# DIO-BNC_CH4-7.net
KiCad netlist of a schematic drawn in Altium Designer
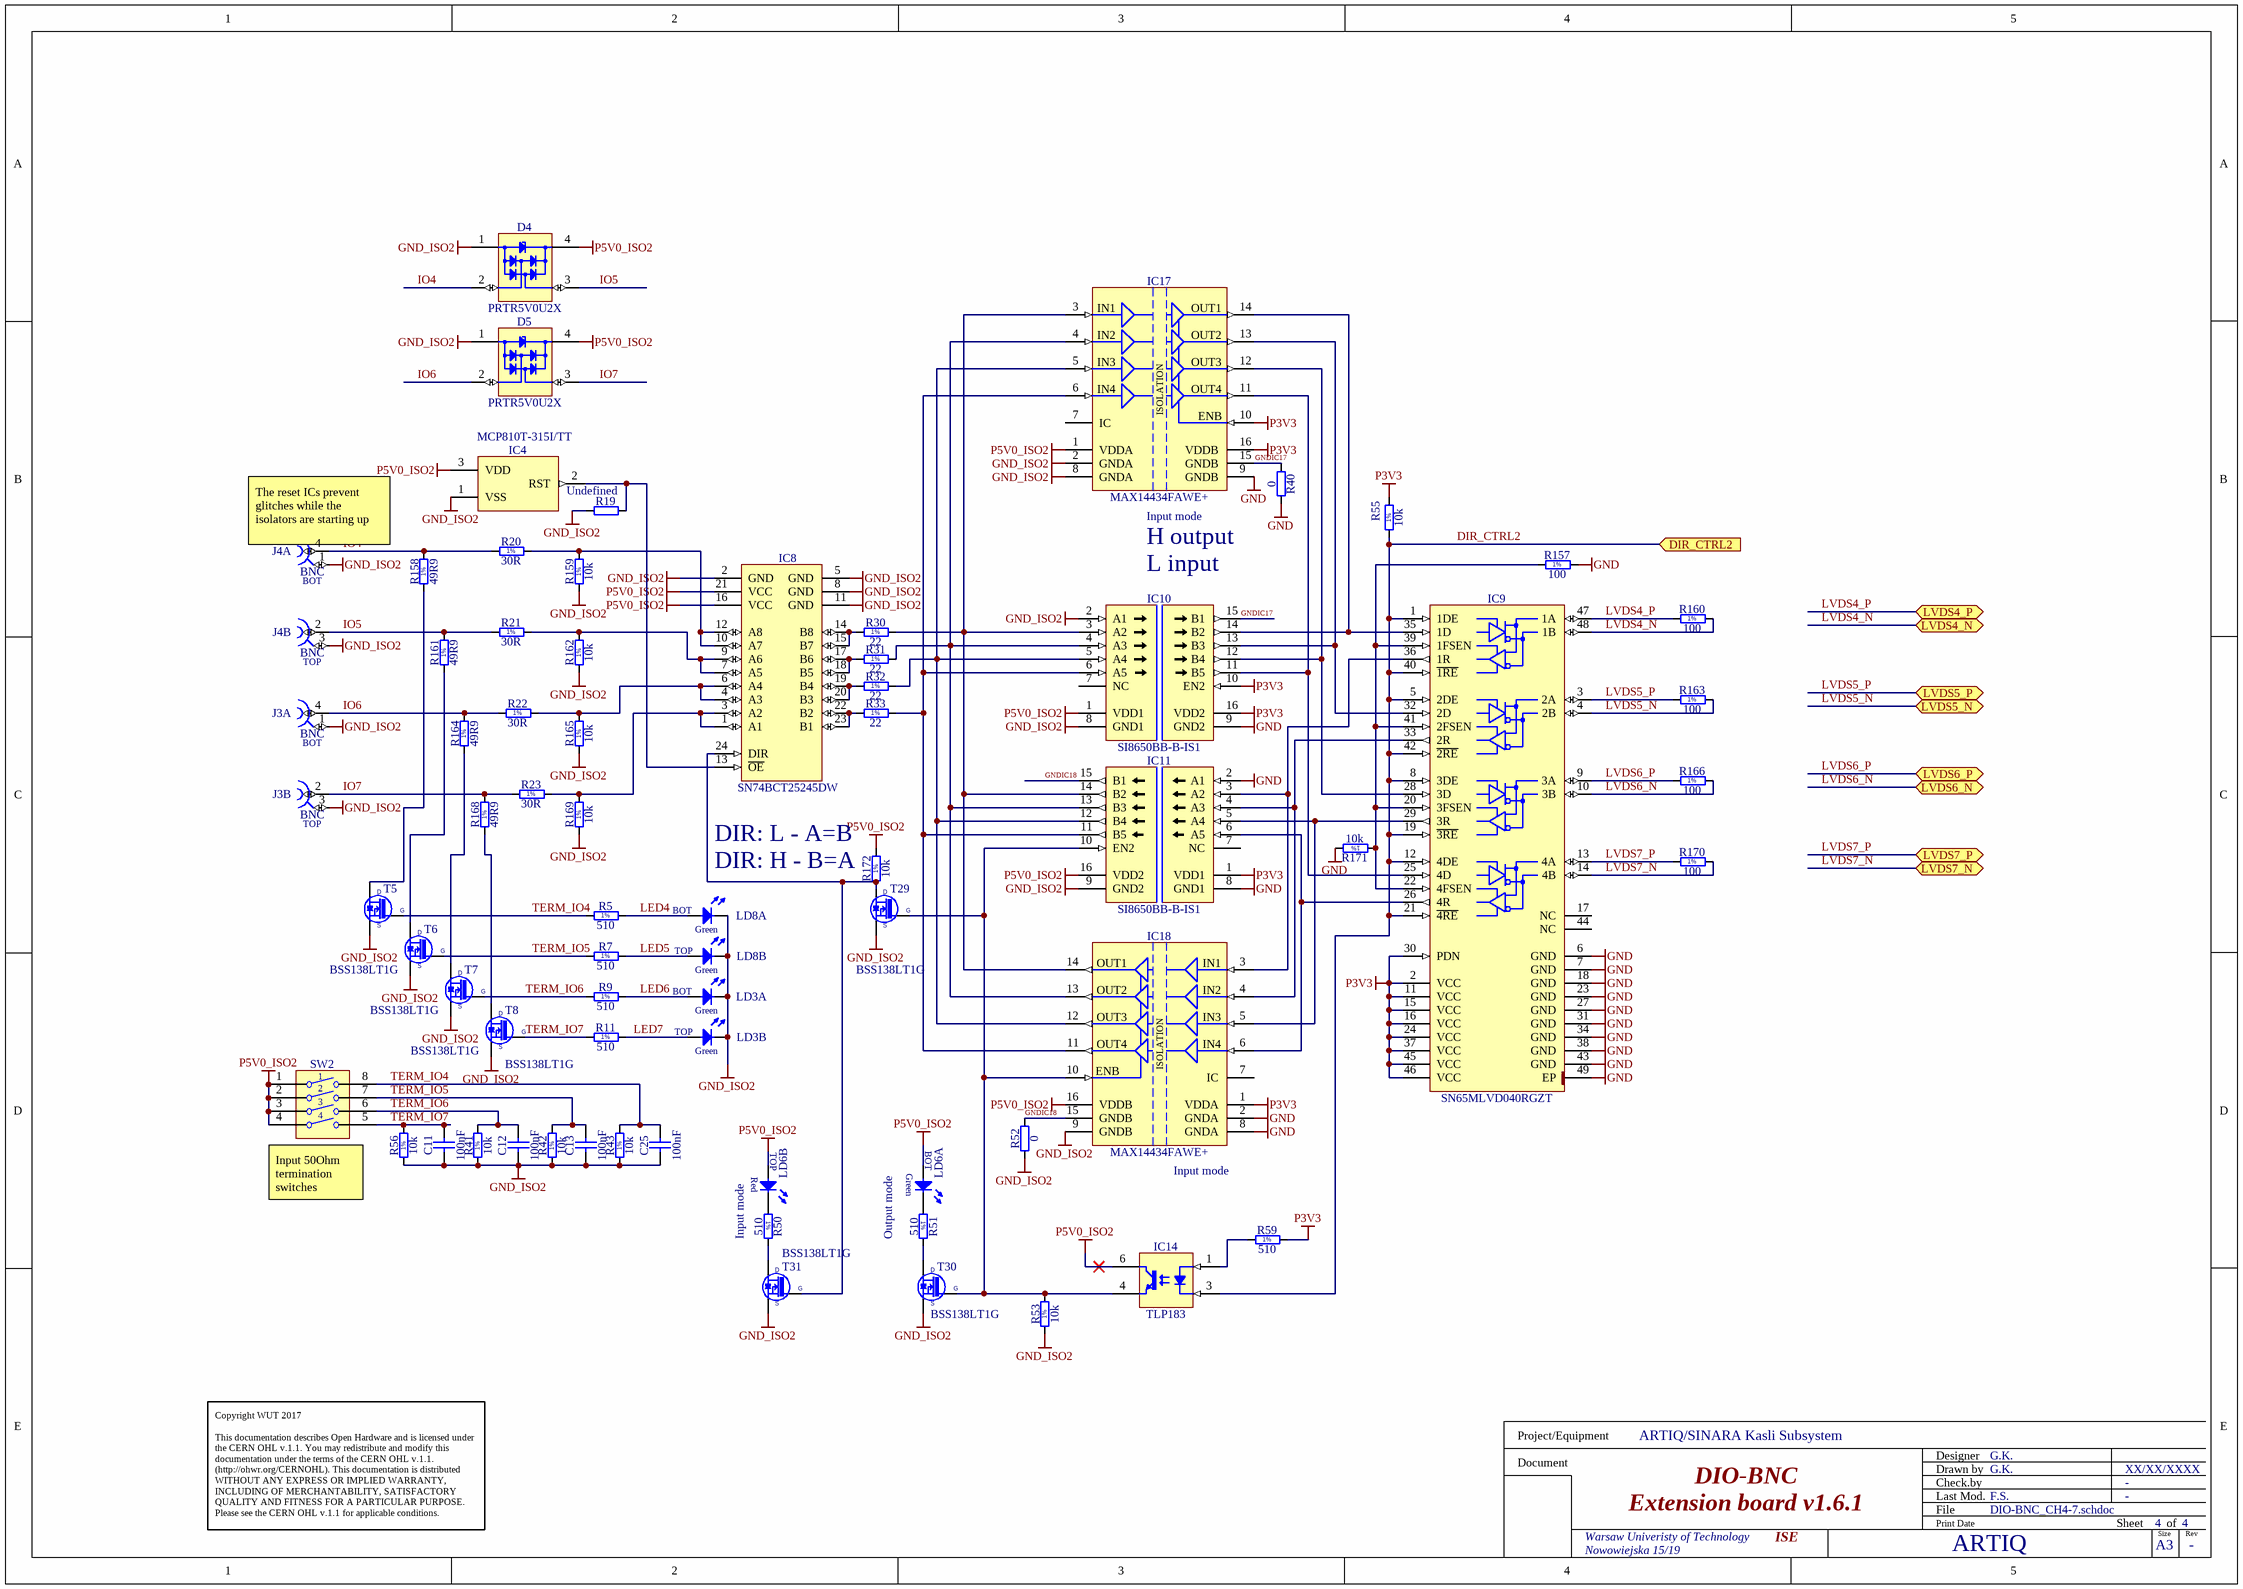
[diagram p0: DIO-BNC_CH4-7.schdoc]

(export (version "E")
  (design (tool "Eeschema 10.0.6"))
  (components
    (comp (ref "C11")
      (value "100nF")
      (footprint "CAPC1005X55N")
      (description "Non-polarised capacitor")
      (fields
        (field (name "PART NUMBER") "CC0402_100NF_16V_10%_X5R")
        (field (name "VOLTAGE") "16V")
        (field (name "AUTHOR") "CERN DEM JLC")
      )
      (libsource (lib "Capacitors") (part "Capacitor - non polarized"))
    )
    (comp (ref "C12")
      (value "100nF")
      (footprint "CAPC1005X55N")
      (description "Non-polarised capacitor")
      (fields
        (field (name "PART NUMBER") "CC0402_100NF_16V_10%_X5R")
        (field (name "VOLTAGE") "16V")
        (field (name "AUTHOR") "CERN DEM JLC")
      )
      (libsource (lib "Capacitors") (part "Capacitor - non polarized"))
    )
    (comp (ref "C13")
      (value "100nF")
      (footprint "CAPC1005X55N")
      (description "Non-polarised capacitor")
      (fields
        (field (name "PART NUMBER") "CC0402_100NF_16V_10%_X5R")
        (field (name "VOLTAGE") "16V")
        (field (name "AUTHOR") "CERN DEM JLC")
      )
      (libsource (lib "Capacitors") (part "Capacitor - non polarized"))
    )
    (comp (ref "C25")
      (value "100nF")
      (footprint "CAPC1005X55N")
      (description "Non-polarised capacitor")
      (fields
        (field (name "PART NUMBER") "CC0402_100NF_16V_10%_X5R")
        (field (name "VOLTAGE") "16V")
        (field (name "AUTHOR") "CERN DEM JLC")
      )
      (libsource (lib "Capacitors") (part "Capacitor - non polarized"))
    )
    (comp (ref "D4")
      (value "PRTR5V0U2X")
      (footprint "SOT190P230X110-4N")
      (description "Ultra Low Capacitance Double Rail-to-Rail ESD Protection Diode")
      (fields
        (field (name "VOLTAGE") "5.5V")
        (field (name "MANUFACTURER") "NXP SEMICONDUCTORS")
        (field (name "AUTHOR") "CERN DEM JLC")
      )
      (libsource (lib "ICs And Semiconductors") (part "PRTR5V0U2X"))
    )
    (comp (ref "D5")
      (value "PRTR5V0U2X")
      (footprint "SOT190P230X110-4N")
      (description "Ultra Low Capacitance Double Rail-to-Rail ESD Protection Diode")
      (fields
        (field (name "VOLTAGE") "5.5V")
        (field (name "MANUFACTURER") "NXP SEMICONDUCTORS")
        (field (name "AUTHOR") "CERN DEM JLC")
      )
      (libsource (lib "ICs And Semiconductors") (part "PRTR5V0U2X"))
    )
    (comp (ref "IC4")
      (value "MCP810T-315I/TT")
      (footprint "SOT95P237X112-3N")
      (description "3.075V Microcontroller Supervisory Circuit With Push-Pull Output")
      (fields (field (name "MANUFACTURER") "MICROCHIP TECHNOLOGY") (field (name "AUTHOR") "GK"))
      (libsource (lib "LIBRARY_SCH") (part "VMON_MCP810"))
    )
    (comp (ref "IC8")
      (value "SN74BCT25245DW")
      (footprint "SOIC127P1030X265-24N")
      (description "25 Ohms Octal Bus Transceiver With 3-State Outputs")
      (fields (field (name "MANUFACTURER") "TEXAS INSTRUMENTS") (field (name "AUTHOR") "CERN DEM JLC"))
      (libsource (lib "ICs And Semiconductors") (part "7425245"))
    )
    (comp (ref "IC9")
      (value "SN65MLVD040RGZT")
      (footprint "QFN50P700X700X100-49N-S420")
      (description "4-Channel Half-Duplex M-LVDS Line Transceiver")
      (fields (field (name "MANUFACTURER") "TEXAS INSTRUMENTS") (field (name "AUTHOR") "CERN DEM JLC"))
      (libsource (lib "ICs And Semiconductors") (part "SN65MLVD040"))
    )
    (comp (ref "IC10")
      (value "SI8650BB-B-IS1")
      (footprint "SOIC127P600X175-16N")
      (description "Low Power Five-Channel Digital Isolator")
      (fields
        (field (name "MANUFACTURER") "SKYWORKS")
        (field (name "MANUFACTURER PART NUMBER") "SI8651BB-B-IS1")
        (field (name "AUTHOR") "CERN DEM HF")
      )
      (libsource (lib "ICs And Semiconductors") (part "Si8650"))
    )
    (comp (ref "IC11")
      (value "SI8650BB-B-IS1")
      (footprint "SOIC127P600X175-16N")
      (description "Low Power Five-Channel Digital Isolator")
      (fields
        (field (name "MANUFACTURER") "SKYWORKS")
        (field (name "MANUFACTURER PART NUMBER") "SI8651BB-B-IS1")
        (field (name "AUTHOR") "CERN DEM HF")
      )
      (libsource (lib "") (part "Si8650_1"))
    )
    (comp (ref "IC14")
      (value "TLP183")
      (footprint "TOSHIBA_11-4M1S")
      (description "Single Optocoupler")
      (fields (field (name "MANUFACTURER") "TOSHIBA") (field (name "AUTHOR") "CERN DEM JMW"))
      (libsource (lib "ICs And Semiconductors") (part "Optocoupler Type1"))
    )
    (comp (ref "IC17")
      (value "MAX14434FAWE+")
      (footprint "SOIC127P1030X265-16N")
      (description "Four-Channel, Fast, Low-Power, 5kVRMS Digital Isolators")
      (fields (field (name "MANUFACTURER") "MAXIM") (field (name "AUTHOR") "CERN DEM HF"))
      (libsource (lib "ICs And Semiconductors") (part "MAX14434"))
    )
    (comp (ref "IC18")
      (value "MAX14434FAWE+")
      (footprint "SOIC127P1030X265-16N")
      (description "Four-Channel, Fast, Low-Power, 5kVRMS Digital Isolators")
      (fields (field (name "MANUFACTURER") "MAXIM") (field (name "AUTHOR") "CERN DEM HF"))
      (libsource (lib "ICs And Semiconductors") (part "MAX14434"))
    )
    (comp (ref "J3")
      (value "BNC")
      (footprint "RENHOTEC_RHT-610-0049")
      (description "Dual Right Angle 50 Ohm BNC Jack, White Valox Case")
      (fields
        (field (name "PART NUMBER") "RENHOTEC_RHT-610-0049")
        (field (name "MANUFACTURER") "RENHOTEC")
        (field (name "AUTHOR") "GK")
      )
      (libsource (lib "LIBRARY_SCH") (part "CON_BNC_DUAL"))
    )
    (comp (ref "J4")
      (value "BNC")
      (footprint "RENHOTEC_RHT-610-0049")
      (description "Dual Right Angle 50 Ohm BNC Jack, White Valox Case")
      (fields
        (field (name "PART NUMBER") "RENHOTEC_RHT-610-0049")
        (field (name "MANUFACTURER") "RENHOTEC")
        (field (name "AUTHOR") "GK")
      )
      (libsource (lib "LIBRARY_SCH") (part "CON_BNC_DUAL"))
    )
    (comp (ref "LD3")
      (value "Green/Green")
      (footprint "LED_DIALIGHT_571-0122F")
      (description "LED x2 Green 1C2A-BOT_3C4A-TOP")
      (fields
        (field (name "PART NUMBER") "LED_DIALIGHT_571-0122F")
        (field (name "MANUFACTURER") "DIALIGHT")
        (field (name "AUTHOR") "CERN DEM JLC")
      )
      (libsource (lib "ICs And Semiconductors") (part "LED x2 Green 1C2A-BOT_3C4A-TOP"))
    )
    (comp (ref "LD6")
      (value "Red/Green")
      (footprint "LED_DIALIGHT_571-0112F")
      (description "2x LED  Botom Green, Top Red")
      (fields
        (field (name "PART NUMBER") "LED_DIALIGHT_571-0112F")
        (field (name "MANUFACTURER") "DIALIGHT")
        (field (name "AUTHOR") "CERN DEM JLC")
      )
      (libsource (lib "ICs And Semiconductors") (part "LED x2 G-1C2A-BOT_R-3C4A-TOP"))
    )
    (comp (ref "LD8")
      (value "Green/Green")
      (footprint "LED_DIALIGHT_571-0122F")
      (description "LED x2 Green 1C2A-BOT_3C4A-TOP")
      (fields
        (field (name "PART NUMBER") "LED_DIALIGHT_571-0122F")
        (field (name "MANUFACTURER") "DIALIGHT")
        (field (name "AUTHOR") "CERN DEM JLC")
      )
      (libsource (lib "ICs And Semiconductors") (part "LED x2 Green 1C2A-BOT_3C4A-TOP"))
    )
    (comp (ref "R5")
      (value "510")
      (footprint "RESC1005X40N")
      (description "Resistor - 1%")
      (fields
        (field (name "PART NUMBER") "R0402_510R_1%_0.0625W_100PPM")
        (field (name "POWER") "0.0625W")
        (field (name "AUTHOR") "CERN DEM JLC")
      )
      (libsource (lib "Resistors") (part "Resistor - 1%"))
    )
    (comp (ref "R7")
      (value "510")
      (footprint "RESC1005X40N")
      (description "Resistor - 1%")
      (fields
        (field (name "PART NUMBER") "R0402_510R_1%_0.0625W_100PPM")
        (field (name "POWER") "0.0625W")
        (field (name "AUTHOR") "CERN DEM JLC")
      )
      (libsource (lib "Resistors") (part "Resistor - 1%"))
    )
    (comp (ref "R9")
      (value "510")
      (footprint "RESC1005X40N")
      (description "Resistor - 1%")
      (fields
        (field (name "PART NUMBER") "R0402_510R_1%_0.0625W_100PPM")
        (field (name "POWER") "0.0625W")
        (field (name "AUTHOR") "CERN DEM JLC")
      )
      (libsource (lib "Resistors") (part "Resistor - 1%"))
    )
    (comp (ref "R11")
      (value "510")
      (footprint "RESC1005X40N")
      (description "Resistor - 1%")
      (fields
        (field (name "PART NUMBER") "R0402_510R_1%_0.0625W_100PPM")
        (field (name "POWER") "0.0625W")
        (field (name "AUTHOR") "CERN DEM JLC")
      )
      (libsource (lib "Resistors") (part "Resistor - 1%"))
    )
    (comp (ref "R19")
      (value "Undefined")
      (footprint "RESC1005X40N")
      (description "Resistor")
      (fields (field (name "PART NUMBER") "R0402_NO-VALUE") (field (name "AUTHOR") "CERN DEM JLC"))
      (libsource (lib "Resistors") (part "Resistor"))
    )
    (comp (ref "R20")
      (value "30R")
      (footprint "RESC3225X70N")
      (description "Resistor - 5%")
      (fields
        (field (name "PART NUMBER") "R1210_30R_5%_0.5W_200ppm")
        (field (name "POWER") "0.5W")
        (field (name "AUTHOR") "CERN DEM JMW")
      )
      (libsource (lib "LIBRARY_SCH") (part "R1210_30R_5%_0.5W_200PPM"))
    )
    (comp (ref "R21")
      (value "30R")
      (footprint "RESC3225X70N")
      (description "Resistor - 5%")
      (fields
        (field (name "PART NUMBER") "R1210_30R_5%_0.5W_200ppm")
        (field (name "POWER") "0.5W")
        (field (name "AUTHOR") "CERN DEM JMW")
      )
      (libsource (lib "LIBRARY_SCH") (part "R1210_30R_5%_0.5W_200PPM"))
    )
    (comp (ref "R22")
      (value "30R")
      (footprint "RESC3225X70N")
      (description "Resistor - 5%")
      (fields
        (field (name "PART NUMBER") "R1210_30R_5%_0.5W_200ppm")
        (field (name "POWER") "0.5W")
        (field (name "AUTHOR") "CERN DEM JMW")
      )
      (libsource (lib "LIBRARY_SCH") (part "R1210_30R_5%_0.5W_200PPM"))
    )
    (comp (ref "R23")
      (value "30R")
      (footprint "RESC3225X70N")
      (description "Resistor - 5%")
      (fields
        (field (name "PART NUMBER") "R1210_30R_5%_0.5W_200ppm")
        (field (name "POWER") "0.5W")
        (field (name "AUTHOR") "CERN DEM JMW")
      )
      (libsource (lib "LIBRARY_SCH") (part "R1210_30R_5%_0.5W_200PPM"))
    )
    (comp (ref "R30")
      (value "22")
      (footprint "RESC1005X40N")
      (description "Resistor - 1%")
      (fields
        (field (name "PART NUMBER") "R0402_22R_1%_0.0625W_100PPM")
        (field (name "POWER") "0.0625W")
        (field (name "AUTHOR") "CERN DEM JLC")
      )
      (libsource (lib "Resistors") (part "Resistor - 1%"))
    )
    (comp (ref "R31")
      (value "22")
      (footprint "RESC1005X40N")
      (description "Resistor - 1%")
      (fields
        (field (name "PART NUMBER") "R0402_22R_1%_0.0625W_100PPM")
        (field (name "POWER") "0.0625W")
        (field (name "AUTHOR") "CERN DEM JLC")
      )
      (libsource (lib "Resistors") (part "Resistor - 1%"))
    )
    (comp (ref "R32")
      (value "22")
      (footprint "RESC1005X40N")
      (description "Resistor - 1%")
      (fields
        (field (name "PART NUMBER") "R0402_22R_1%_0.0625W_100PPM")
        (field (name "POWER") "0.0625W")
        (field (name "AUTHOR") "CERN DEM JLC")
      )
      (libsource (lib "Resistors") (part "Resistor - 1%"))
    )
    (comp (ref "R33")
      (value "22")
      (footprint "RESC1005X40N")
      (description "Resistor - 1%")
      (fields
        (field (name "PART NUMBER") "R0402_22R_1%_0.0625W_100PPM")
        (field (name "POWER") "0.0625W")
        (field (name "AUTHOR") "CERN DEM JLC")
      )
      (libsource (lib "Resistors") (part "Resistor - 1%"))
    )
    (comp (ref "R40")
      (value "0")
      (footprint "RESC1005X40N")
      (description "Resistor")
      (fields
        (field (name "PART NUMBER") "R0402_0R_JUMPER")
        (field (name "MANUFACTURER") "GENERIC")
        (field (name "AUTHOR") "CERN DEM JLC")
      )
      (libsource (lib "Resistors") (part "Resistor"))
    )
    (comp (ref "R41")
      (value "10k")
      (footprint "RESC1005X40N")
      (description "Resistor - 1%")
      (fields
        (field (name "PART NUMBER") "R0402_10K_1%_0.0625W_100PPM")
        (field (name "POWER") "0.0625W")
        (field (name "AUTHOR") "CERN DEM JLC")
      )
      (libsource (lib "Resistors") (part "Resistor - 1%"))
    )
    (comp (ref "R42")
      (value "10k")
      (footprint "RESC1005X40N")
      (description "Resistor - 1%")
      (fields
        (field (name "PART NUMBER") "R0402_10K_1%_0.0625W_100PPM")
        (field (name "POWER") "0.0625W")
        (field (name "AUTHOR") "CERN DEM JLC")
      )
      (libsource (lib "Resistors") (part "Resistor - 1%"))
    )
    (comp (ref "R43")
      (value "10k")
      (footprint "RESC1005X40N")
      (description "Resistor - 1%")
      (fields
        (field (name "PART NUMBER") "R0402_10K_1%_0.0625W_100PPM")
        (field (name "POWER") "0.0625W")
        (field (name "AUTHOR") "CERN DEM JLC")
      )
      (libsource (lib "Resistors") (part "Resistor - 1%"))
    )
    (comp (ref "R50")
      (value "510")
      (footprint "RESC1005X40N")
      (description "Resistor - 1%")
      (fields
        (field (name "PART NUMBER") "R0402_510R_1%_0.0625W_100PPM")
        (field (name "POWER") "0.0625W")
        (field (name "AUTHOR") "CERN DEM JLC")
      )
      (libsource (lib "Resistors") (part "Resistor - 1%"))
    )
    (comp (ref "R51")
      (value "510")
      (footprint "RESC1005X40N")
      (description "Resistor - 1%")
      (fields
        (field (name "PART NUMBER") "R0402_510R_1%_0.0625W_100PPM")
        (field (name "POWER") "0.0625W")
        (field (name "AUTHOR") "CERN DEM JLC")
      )
      (libsource (lib "Resistors") (part "Resistor - 1%"))
    )
    (comp (ref "R52")
      (value "0")
      (footprint "RESC1005X40N")
      (description "Resistor")
      (fields
        (field (name "PART NUMBER") "R0402_0R_JUMPER")
        (field (name "MANUFACTURER") "GENERIC")
        (field (name "AUTHOR") "CERN DEM JLC")
      )
      (libsource (lib "Resistors") (part "Resistor"))
    )
    (comp (ref "R53")
      (value "10k")
      (footprint "RESC1005X40N")
      (description "Resistor - 1%")
      (fields
        (field (name "PART NUMBER") "R0402_10K_1%_0.0625W_100PPM")
        (field (name "POWER") "0.0625W")
        (field (name "AUTHOR") "CERN DEM JLC")
      )
      (libsource (lib "Resistors") (part "Resistor - 1%"))
    )
    (comp (ref "R55")
      (value "10k")
      (footprint "RESC1005X40N")
      (description "Resistor - 1%")
      (fields
        (field (name "PART NUMBER") "R0402_10K_1%_0.0625W_100PPM")
        (field (name "POWER") "0.0625W")
        (field (name "AUTHOR") "CERN DEM JLC")
      )
      (libsource (lib "Resistors") (part "Resistor - 1%"))
    )
    (comp (ref "R56")
      (value "10k")
      (footprint "RESC1005X40N")
      (description "Resistor - 1%")
      (fields
        (field (name "PART NUMBER") "R0402_10K_1%_0.0625W_100PPM")
        (field (name "POWER") "0.0625W")
        (field (name "AUTHOR") "CERN DEM JLC")
      )
      (libsource (lib "Resistors") (part "Resistor - 1%"))
    )
    (comp (ref "R59")
      (value "510")
      (footprint "RESC1005X40N")
      (description "Resistor - 1%")
      (fields
        (field (name "PART NUMBER") "R0402_510R_1%_0.0625W_100PPM")
        (field (name "POWER") "0.0625W")
        (field (name "AUTHOR") "CERN DEM JLC")
      )
      (libsource (lib "Resistors") (part "Resistor - 1%"))
    )
    (comp (ref "R157")
      (value "100")
      (footprint "RESC1005X40N")
      (description "Resistor - 1%")
      (fields
        (field (name "PART NUMBER") "R0402_100R_1%_0.1W_100PPM")
        (field (name "POWER") "0.1W")
        (field (name "AUTHOR") "CERN DEM JLC")
      )
      (libsource (lib "Resistors") (part "Resistor - 1%"))
    )
    (comp (ref "R158")
      (value "49R9")
      (footprint "RESC3225X70N")
      (description "Resistor - 1%")
      (fields
        (field (name "PART NUMBER") "R1210_49R9_1%_0.5W_100PPM_VISHAY_CRCW")
        (field (name "POWER") "0.5W")
        (field (name "AUTHOR") "CERN DEM JMW")
      )
      (libsource (lib "Resistors") (part "Resistor - 1%"))
    )
    (comp (ref "R159")
      (value "10k")
      (footprint "RESC1005X40N")
      (description "Resistor - 1%")
      (fields
        (field (name "PART NUMBER") "R0402_10K_1%_0.0625W_100PPM")
        (field (name "POWER") "0.0625W")
        (field (name "AUTHOR") "CERN DEM JLC")
      )
      (libsource (lib "Resistors") (part "Resistor - 1%"))
    )
    (comp (ref "R160")
      (value "100")
      (footprint "RESC1005X40N")
      (description "Resistor - 1%")
      (fields
        (field (name "PART NUMBER") "R0402_100R_1%_0.1W_100PPM")
        (field (name "POWER") "0.1W")
        (field (name "AUTHOR") "CERN DEM JLC")
      )
      (libsource (lib "Resistors") (part "Resistor - 1%"))
    )
    (comp (ref "R161")
      (value "49R9")
      (footprint "RESC3225X70N")
      (description "Resistor - 1%")
      (fields
        (field (name "PART NUMBER") "R1210_49R9_1%_0.5W_100PPM_VISHAY_CRCW")
        (field (name "POWER") "0.5W")
        (field (name "AUTHOR") "CERN DEM JMW")
      )
      (libsource (lib "Resistors") (part "Resistor - 1%"))
    )
    (comp (ref "R162")
      (value "10k")
      (footprint "RESC1005X40N")
      (description "Resistor - 1%")
      (fields
        (field (name "PART NUMBER") "R0402_10K_1%_0.0625W_100PPM")
        (field (name "POWER") "0.0625W")
        (field (name "AUTHOR") "CERN DEM JLC")
      )
      (libsource (lib "Resistors") (part "Resistor - 1%"))
    )
    (comp (ref "R163")
      (value "100")
      (footprint "RESC1005X40N")
      (description "Resistor - 1%")
      (fields
        (field (name "PART NUMBER") "R0402_100R_1%_0.1W_100PPM")
        (field (name "POWER") "0.1W")
        (field (name "AUTHOR") "CERN DEM JLC")
      )
      (libsource (lib "Resistors") (part "Resistor - 1%"))
    )
    (comp (ref "R164")
      (value "49R9")
      (footprint "RESC3225X70N")
      (description "Resistor - 1%")
      (fields
        (field (name "PART NUMBER") "R1210_49R9_1%_0.5W_100PPM_VISHAY_CRCW")
        (field (name "POWER") "0.5W")
        (field (name "AUTHOR") "CERN DEM JMW")
      )
      (libsource (lib "Resistors") (part "Resistor - 1%"))
    )
    (comp (ref "R165")
      (value "10k")
      (footprint "RESC1005X40N")
      (description "Resistor - 1%")
      (fields
        (field (name "PART NUMBER") "R0402_10K_1%_0.0625W_100PPM")
        (field (name "POWER") "0.0625W")
        (field (name "AUTHOR") "CERN DEM JLC")
      )
      (libsource (lib "Resistors") (part "Resistor - 1%"))
    )
    (comp (ref "R166")
      (value "100")
      (footprint "RESC1005X40N")
      (description "Resistor - 1%")
      (fields
        (field (name "PART NUMBER") "R0402_100R_1%_0.1W_100PPM")
        (field (name "POWER") "0.1W")
        (field (name "AUTHOR") "CERN DEM JLC")
      )
      (libsource (lib "Resistors") (part "Resistor - 1%"))
    )
    (comp (ref "R168")
      (value "49R9")
      (footprint "RESC3225X70N")
      (description "Resistor - 1%")
      (fields
        (field (name "PART NUMBER") "R1210_49R9_1%_0.5W_100PPM_VISHAY_CRCW")
        (field (name "POWER") "0.5W")
        (field (name "AUTHOR") "CERN DEM JMW")
      )
      (libsource (lib "Resistors") (part "Resistor - 1%"))
    )
    (comp (ref "R169")
      (value "10k")
      (footprint "RESC1005X40N")
      (description "Resistor - 1%")
      (fields
        (field (name "PART NUMBER") "R0402_10K_1%_0.0625W_100PPM")
        (field (name "POWER") "0.0625W")
        (field (name "AUTHOR") "CERN DEM JLC")
      )
      (libsource (lib "Resistors") (part "Resistor - 1%"))
    )
    (comp (ref "R170")
      (value "100")
      (footprint "RESC1005X40N")
      (description "Resistor - 1%")
      (fields
        (field (name "PART NUMBER") "R0402_100R_1%_0.1W_100PPM")
        (field (name "POWER") "0.1W")
        (field (name "AUTHOR") "CERN DEM JLC")
      )
      (libsource (lib "Resistors") (part "Resistor - 1%"))
    )
    (comp (ref "R171")
      (value "10k")
      (footprint "RESC1005X40N")
      (description "Resistor - 1%")
      (fields
        (field (name "PART NUMBER") "R0402_10K_1%_0.0625W_100PPM")
        (field (name "POWER") "0.0625W")
        (field (name "AUTHOR") "CERN DEM JLC")
      )
      (libsource (lib "Resistors") (part "Resistor - 1%"))
    )
    (comp (ref "R172")
      (value "10k")
      (footprint "RESC1005X40N")
      (description "Resistor - 1%")
      (fields
        (field (name "PART NUMBER") "R0402_10K_1%_0.0625W_100PPM")
        (field (name "POWER") "0.0625W")
        (field (name "AUTHOR") "CERN DEM JLC")
      )
      (libsource (lib "Resistors") (part "Resistor - 1%"))
    )
    (comp (ref "SW2")
      (value "Switch")
      (footprint "SW_OMRON_A6S-4102-H")
      (description "4 Ways SPST DIP Switch")
      (fields
        (field (name "PART NUMBER") "SW_OMRON_A6S-4102-H")
        (field (name "MANUFACTURER") "OMRON")
        (field (name "AUTHOR") "CERN DEM JMW")
      )
      (libsource (lib "Eletro-mechanical") (part "SW 4x SPST DIP Switch"))
    )
    (comp (ref "T5")
      (value "BSS138LT1G")
      (footprint "SOT95P240X110-3N")
      (description "N-CHANNEL MOSFET WITH DIODE")
      (fields (field (name "MANUFACTURER") "ON SEMICONDUCTOR") (field (name "AUTHOR") "CERN DEM JLC"))
      (libsource (lib "ICs And Semiconductors") (part "N-MOSFET-D 1G 2S 3D"))
    )
    (comp (ref "T6")
      (value "BSS138LT1G")
      (footprint "SOT95P240X110-3N")
      (description "N-CHANNEL MOSFET WITH DIODE")
      (fields (field (name "MANUFACTURER") "ON SEMICONDUCTOR") (field (name "AUTHOR") "CERN DEM JLC"))
      (libsource (lib "ICs And Semiconductors") (part "N-MOSFET-D 1G 2S 3D"))
    )
    (comp (ref "T7")
      (value "BSS138LT1G")
      (footprint "SOT95P240X110-3N")
      (description "N-CHANNEL MOSFET WITH DIODE")
      (fields (field (name "MANUFACTURER") "ON SEMICONDUCTOR") (field (name "AUTHOR") "CERN DEM JLC"))
      (libsource (lib "ICs And Semiconductors") (part "N-MOSFET-D 1G 2S 3D"))
    )
    (comp (ref "T8")
      (value "BSS138LT1G")
      (footprint "SOT95P240X110-3N")
      (description "N-CHANNEL MOSFET WITH DIODE")
      (fields (field (name "MANUFACTURER") "ON SEMICONDUCTOR") (field (name "AUTHOR") "CERN DEM JLC"))
      (libsource (lib "ICs And Semiconductors") (part "N-MOSFET-D 1G 2S 3D"))
    )
    (comp (ref "T29")
      (value "BSS138LT1G")
      (footprint "SOT95P240X110-3N")
      (description "N-CHANNEL MOSFET WITH DIODE")
      (fields (field (name "MANUFACTURER") "ON SEMICONDUCTOR") (field (name "AUTHOR") "CERN DEM JLC"))
      (libsource (lib "ICs And Semiconductors") (part "N-MOSFET-D 1G 2S 3D"))
    )
    (comp (ref "T30")
      (value "BSS138LT1G")
      (footprint "SOT95P240X110-3N")
      (description "N-CHANNEL MOSFET WITH DIODE")
      (fields (field (name "MANUFACTURER") "ON SEMICONDUCTOR") (field (name "AUTHOR") "CERN DEM JLC"))
      (libsource (lib "ICs And Semiconductors") (part "N-MOSFET-D 1G 2S 3D"))
    )
    (comp (ref "T31")
      (value "BSS138LT1G")
      (footprint "SOT95P240X110-3N")
      (description "N-CHANNEL MOSFET WITH DIODE")
      (fields (field (name "MANUFACTURER") "ON SEMICONDUCTOR") (field (name "AUTHOR") "CERN DEM JLC"))
      (libsource (lib "ICs And Semiconductors") (part "N-MOSFET-D 1G 2S 3D"))
    )
  )
  (nets
    (net (code "1") (name "/DIR_CTRL2") (class "Default")
      (node (ref "IC14") (pin "3") (pinfunction "C_3") (pintype "input"))
      (node (ref "IC9") (pin "1") (pinfunction "1DE_1") (pintype "input"))
      (node (ref "IC9") (pin "12") (pinfunction "4DE_12") (pintype "input"))
      (node (ref "IC9") (pin "19") (pinfunction "~{3RE}_19") (pintype "input"))
      (node (ref "IC9") (pin "21") (pinfunction "~{4RE}_21") (pintype "input"))
      (node (ref "IC9") (pin "40") (pinfunction "~{1RE}_40") (pintype "input"))
      (node (ref "IC9") (pin "42") (pinfunction "~{2RE}_42") (pintype "input"))
      (node (ref "IC9") (pin "5") (pinfunction "2DE_5") (pintype "input"))
      (node (ref "IC9") (pin "8") (pinfunction "3DE_8") (pintype "input"))
      (node (ref "R55") (pin "1") (pinfunction "1_1") (pintype "passive"))
    )
    (net (code "2") (name "/GNDIC17") (class "Default")
      (node (ref "IC10") (pin "15") (pinfunction "B1_15") (pintype "output"))
      (node (ref "IC17") (pin "15") (pinfunction "GNDB_15") (pintype "power_in"))
      (node (ref "R40") (pin "1") (pinfunction "1_1") (pintype "passive"))
    )
    (net (code "3") (name "/GNDIC18") (class "Default")
      (node (ref "IC11") (pin "15") (pinfunction "B1_15") (pintype "output"))
      (node (ref "IC18") (pin "15") (pinfunction "GNDB_15") (pintype "power_in"))
      (node (ref "R52") (pin "1") (pinfunction "1_1") (pintype "passive"))
    )
    (net (code "4") (name "/IO4") (class "Default")
      (node (ref "D4") (pin "2") (pinfunction "I/O1_2") (pintype "bidirectional"))
      (node (ref "J4") (pin "4") (pinfunction "4_4") (pintype "bidirectional"))
      (node (ref "R158") (pin "2") (pinfunction "2_2") (pintype "passive"))
      (node (ref "R20") (pin "1") (pinfunction "1_1") (pintype "passive"))
    )
    (net (code "5") (name "/IO5") (class "Default")
      (node (ref "D4") (pin "3") (pinfunction "I/O2_3") (pintype "bidirectional"))
      (node (ref "J4") (pin "2") (pinfunction "2_2") (pintype "bidirectional"))
      (node (ref "R161") (pin "2") (pinfunction "2_2") (pintype "passive"))
      (node (ref "R21") (pin "1") (pinfunction "1_1") (pintype "passive"))
    )
    (net (code "6") (name "/IO6") (class "Default")
      (node (ref "D5") (pin "2") (pinfunction "I/O1_2") (pintype "bidirectional"))
      (node (ref "J3") (pin "4") (pinfunction "4_4") (pintype "bidirectional"))
      (node (ref "R164") (pin "2") (pinfunction "2_2") (pintype "passive"))
      (node (ref "R22") (pin "1") (pinfunction "1_1") (pintype "passive"))
    )
    (net (code "7") (name "/IO7") (class "Default")
      (node (ref "D5") (pin "3") (pinfunction "I/O2_3") (pintype "bidirectional"))
      (node (ref "J3") (pin "2") (pinfunction "2_2") (pintype "bidirectional"))
      (node (ref "R168") (pin "2") (pinfunction "2_2") (pintype "passive"))
      (node (ref "R23") (pin "1") (pinfunction "1_1") (pintype "passive"))
    )
    (net (code "8") (name "/LED4") (class "Default")
      (node (ref "LD8") (pin "2") (pinfunction "A_2") (pintype "passive"))
      (node (ref "R5") (pin "2") (pinfunction "2_2") (pintype "passive"))
    )
    (net (code "9") (name "/LED5") (class "Default")
      (node (ref "LD8") (pin "4") (pinfunction "A_4") (pintype "passive"))
      (node (ref "R7") (pin "2") (pinfunction "2_2") (pintype "passive"))
    )
    (net (code "10") (name "/LED6") (class "Default")
      (node (ref "LD3") (pin "2") (pinfunction "A_2") (pintype "passive"))
      (node (ref "R9") (pin "2") (pinfunction "2_2") (pintype "passive"))
    )
    (net (code "11") (name "/LED7") (class "Default")
      (node (ref "LD3") (pin "4") (pinfunction "A_4") (pintype "passive"))
      (node (ref "R11") (pin "2") (pinfunction "2_2") (pintype "passive"))
    )
    (net (code "12") (name "/LVDS4_N") (class "Default")
      (node (ref "IC9") (pin "48") (pinfunction "1B_48") (pintype "bidirectional"))
      (node (ref "R160") (pin "2") (pinfunction "2_2") (pintype "passive"))
    )
    (net (code "13") (name "/LVDS4_P") (class "Default")
      (node (ref "IC9") (pin "47") (pinfunction "1A_47") (pintype "bidirectional"))
      (node (ref "R160") (pin "1") (pinfunction "1_1") (pintype "passive"))
    )
    (net (code "14") (name "/LVDS5_N") (class "Default")
      (node (ref "IC9") (pin "4") (pinfunction "2B_4") (pintype "bidirectional"))
      (node (ref "R163") (pin "2") (pinfunction "2_2") (pintype "passive"))
    )
    (net (code "15") (name "/LVDS5_P") (class "Default")
      (node (ref "IC9") (pin "3") (pinfunction "2A_3") (pintype "bidirectional"))
      (node (ref "R163") (pin "1") (pinfunction "1_1") (pintype "passive"))
    )
    (net (code "16") (name "/LVDS6_N") (class "Default")
      (node (ref "IC9") (pin "10") (pinfunction "3B_10") (pintype "bidirectional"))
      (node (ref "R166") (pin "2") (pinfunction "2_2") (pintype "passive"))
    )
    (net (code "17") (name "/LVDS6_P") (class "Default")
      (node (ref "IC9") (pin "9") (pinfunction "3A_9") (pintype "bidirectional"))
      (node (ref "R166") (pin "1") (pinfunction "1_1") (pintype "passive"))
    )
    (net (code "18") (name "/LVDS7_N") (class "Default")
      (node (ref "IC9") (pin "14") (pinfunction "4B_14") (pintype "bidirectional"))
      (node (ref "R170") (pin "2") (pinfunction "2_2") (pintype "passive"))
    )
    (net (code "19") (name "/LVDS7_P") (class "Default")
      (node (ref "IC9") (pin "13") (pinfunction "4A_13") (pintype "bidirectional"))
      (node (ref "R170") (pin "1") (pinfunction "1_1") (pintype "passive"))
    )
    (net (code "20") (name "/TERM_IO4") (class "Default")
      (node (ref "C25") (pin "2") (pinfunction "2_2") (pintype "passive"))
      (node (ref "R43") (pin "2") (pinfunction "2_2") (pintype "passive"))
      (node (ref "R5") (pin "1") (pinfunction "1_1") (pintype "passive"))
      (node (ref "SW2") (pin "8") (pinfunction "8_8") (pintype "passive"))
      (node (ref "T5") (pin "1") (pinfunction "G_1") (pintype "passive"))
    )
    (net (code "21") (name "/TERM_IO5") (class "Default")
      (node (ref "C13") (pin "2") (pinfunction "2_2") (pintype "passive"))
      (node (ref "R42") (pin "2") (pinfunction "2_2") (pintype "passive"))
      (node (ref "R7") (pin "1") (pinfunction "1_1") (pintype "passive"))
      (node (ref "SW2") (pin "7") (pinfunction "7_7") (pintype "passive"))
      (node (ref "T6") (pin "1") (pinfunction "G_1") (pintype "passive"))
    )
    (net (code "22") (name "/TERM_IO6") (class "Default")
      (node (ref "C12") (pin "2") (pinfunction "2_2") (pintype "passive"))
      (node (ref "R41") (pin "2") (pinfunction "2_2") (pintype "passive"))
      (node (ref "R9") (pin "1") (pinfunction "1_1") (pintype "passive"))
      (node (ref "SW2") (pin "6") (pinfunction "6_6") (pintype "passive"))
      (node (ref "T7") (pin "1") (pinfunction "G_1") (pintype "passive"))
    )
    (net (code "23") (name "/TERM_IO7") (class "Default")
      (node (ref "C11") (pin "2") (pinfunction "2_2") (pintype "passive"))
      (node (ref "R11") (pin "1") (pinfunction "1_1") (pintype "passive"))
      (node (ref "R56") (pin "2") (pinfunction "2_2") (pintype "passive"))
      (node (ref "SW2") (pin "5") (pinfunction "5_5") (pintype "passive"))
      (node (ref "T8") (pin "1") (pinfunction "G_1") (pintype "passive"))
    )
    (net (code "24") (name "GND") (class "Default")
      (node (ref "IC10") (pin "9") (pinfunction "GND2_9") (pintype "power_in"))
      (node (ref "IC11") (pin "2") (pinfunction "A1_2") (pintype "input"))
      (node (ref "IC11") (pin "8") (pinfunction "GND1_8") (pintype "power_in"))
      (node (ref "IC17") (pin "9") (pinfunction "GNDB_9") (pintype "power_in"))
      (node (ref "IC18") (pin "2") (pinfunction "GNDA_2") (pintype "power_in"))
      (node (ref "IC18") (pin "8") (pinfunction "GNDA_8") (pintype "power_in"))
      (node (ref "IC9") (pin "18") (pinfunction "GND_18") (pintype "power_in"))
      (node (ref "IC9") (pin "23") (pinfunction "GND_23") (pintype "power_in"))
      (node (ref "IC9") (pin "27") (pinfunction "GND_27") (pintype "power_in"))
      (node (ref "IC9") (pin "31") (pinfunction "GND_31") (pintype "power_in"))
      (node (ref "IC9") (pin "34") (pinfunction "GND_34") (pintype "power_in"))
      (node (ref "IC9") (pin "38") (pinfunction "GND_38") (pintype "power_in"))
      (node (ref "IC9") (pin "43") (pinfunction "GND_43") (pintype "power_in"))
      (node (ref "IC9") (pin "49") (pinfunction "EP_49") (pintype "power_in"))
      (node (ref "IC9") (pin "6") (pinfunction "GND_6") (pintype "power_in"))
      (node (ref "IC9") (pin "7") (pinfunction "GND_7") (pintype "power_in"))
      (node (ref "R157") (pin "2") (pinfunction "2_2") (pintype "passive"))
      (node (ref "R171") (pin "2") (pinfunction "2_2") (pintype "passive"))
      (node (ref "R40") (pin "2") (pinfunction "2_2") (pintype "passive"))
    )
    (net (code "25") (name "GND_ISO2") (class "Default")
      (node (ref "C11") (pin "1") (pinfunction "1_1") (pintype "passive"))
      (node (ref "C12") (pin "1") (pinfunction "1_1") (pintype "passive"))
      (node (ref "C13") (pin "1") (pinfunction "1_1") (pintype "passive"))
      (node (ref "C25") (pin "1") (pinfunction "1_1") (pintype "passive"))
      (node (ref "D4") (pin "1") (pinfunction "GND_1") (pintype "power_in"))
      (node (ref "D5") (pin "1") (pinfunction "GND_1") (pintype "power_in"))
      (node (ref "IC10") (pin "2") (pinfunction "A1_2") (pintype "input"))
      (node (ref "IC10") (pin "8") (pinfunction "GND1_8") (pintype "power_in"))
      (node (ref "IC11") (pin "9") (pinfunction "GND2_9") (pintype "power_in"))
      (node (ref "IC17") (pin "2") (pinfunction "GNDA_2") (pintype "power_in"))
      (node (ref "IC17") (pin "8") (pinfunction "GNDA_8") (pintype "power_in"))
      (node (ref "IC18") (pin "9") (pinfunction "GNDB_9") (pintype "power_in"))
      (node (ref "IC4") (pin "1") (pinfunction "VSS_1") (pintype "power_in"))
      (node (ref "IC8") (pin "11") (pinfunction "GND_11") (pintype "power_in"))
      (node (ref "IC8") (pin "2") (pinfunction "GND_2") (pintype "power_in"))
      (node (ref "IC8") (pin "5") (pinfunction "GND_5") (pintype "power_in"))
      (node (ref "IC8") (pin "8") (pinfunction "GND_8") (pintype "power_in"))
      (node (ref "J3") (pin "1") (pinfunction "1_1") (pintype "bidirectional"))
      (node (ref "J3") (pin "3") (pinfunction "3_3") (pintype "bidirectional"))
      (node (ref "J4") (pin "1") (pinfunction "1_1") (pintype "bidirectional"))
      (node (ref "J4") (pin "3") (pinfunction "3_3") (pintype "bidirectional"))
      (node (ref "LD3") (pin "1") (pinfunction "C_1") (pintype "passive"))
      (node (ref "LD3") (pin "3") (pinfunction "C_3") (pintype "passive"))
      (node (ref "LD8") (pin "1") (pinfunction "C_1") (pintype "passive"))
      (node (ref "LD8") (pin "3") (pinfunction "C_3") (pintype "passive"))
      (node (ref "R159") (pin "1") (pinfunction "1_1") (pintype "passive"))
      (node (ref "R162") (pin "1") (pinfunction "1_1") (pintype "passive"))
      (node (ref "R165") (pin "1") (pinfunction "1_1") (pintype "passive"))
      (node (ref "R169") (pin "1") (pinfunction "1_1") (pintype "passive"))
      (node (ref "R19") (pin "1") (pinfunction "1_1") (pintype "passive"))
      (node (ref "R41") (pin "1") (pinfunction "1_1") (pintype "passive"))
      (node (ref "R42") (pin "1") (pinfunction "1_1") (pintype "passive"))
      (node (ref "R43") (pin "1") (pinfunction "1_1") (pintype "passive"))
      (node (ref "R52") (pin "2") (pinfunction "2_2") (pintype "passive"))
      (node (ref "R53") (pin "1") (pinfunction "1_1") (pintype "passive"))
      (node (ref "R56") (pin "1") (pinfunction "1_1") (pintype "passive"))
      (node (ref "T29") (pin "2") (pinfunction "S_2") (pintype "passive"))
      (node (ref "T30") (pin "2") (pinfunction "S_2") (pintype "passive"))
      (node (ref "T31") (pin "2") (pinfunction "S_2") (pintype "passive"))
      (node (ref "T5") (pin "2") (pinfunction "S_2") (pintype "passive"))
      (node (ref "T6") (pin "2") (pinfunction "S_2") (pintype "passive"))
      (node (ref "T7") (pin "2") (pinfunction "S_2") (pintype "passive"))
      (node (ref "T8") (pin "2") (pinfunction "S_2") (pintype "passive"))
    )
    (net (code "26") (name "Net-(IC4-RST)") (class "Default")
      (node (ref "IC4") (pin "2") (pinfunction "RST_2") (pintype "output"))
      (node (ref "IC8") (pin "13") (pinfunction "OE_13") (pintype "input"))
      (node (ref "R19") (pin "2") (pinfunction "2_2") (pintype "passive"))
    )
    (net (code "27") (name "Net-(IC8-A1)") (class "Default")
      (node (ref "IC8") (pin "1") (pinfunction "A1_1") (pintype "bidirectional"))
      (node (ref "IC8") (pin "3") (pinfunction "A2_3") (pintype "bidirectional"))
      (node (ref "R169") (pin "2") (pinfunction "2_2") (pintype "passive"))
      (node (ref "R23") (pin "2") (pinfunction "2_2") (pintype "passive"))
    )
    (net (code "28") (name "Net-(IC8-A3)") (class "Default")
      (node (ref "IC8") (pin "4") (pinfunction "A3_4") (pintype "bidirectional"))
      (node (ref "IC8") (pin "6") (pinfunction "A4_6") (pintype "bidirectional"))
      (node (ref "R165") (pin "2") (pinfunction "2_2") (pintype "passive"))
      (node (ref "R22") (pin "2") (pinfunction "2_2") (pintype "passive"))
    )
    (net (code "29") (name "Net-(IC8-A5)") (class "Default")
      (node (ref "IC8") (pin "7") (pinfunction "A5_7") (pintype "bidirectional"))
      (node (ref "IC8") (pin "9") (pinfunction "A6_9") (pintype "bidirectional"))
      (node (ref "R162") (pin "2") (pinfunction "2_2") (pintype "passive"))
      (node (ref "R21") (pin "2") (pinfunction "2_2") (pintype "passive"))
    )
    (net (code "30") (name "Net-(IC8-A7)") (class "Default")
      (node (ref "IC8") (pin "10") (pinfunction "A7_10") (pintype "bidirectional"))
      (node (ref "IC8") (pin "12") (pinfunction "A8_12") (pintype "bidirectional"))
      (node (ref "R159") (pin "2") (pinfunction "2_2") (pintype "passive"))
      (node (ref "R20") (pin "2") (pinfunction "2_2") (pintype "passive"))
    )
    (net (code "31") (name "Net-(IC8-B1)") (class "Default")
      (node (ref "IC8") (pin "22") (pinfunction "B2_22") (pintype "bidirectional"))
      (node (ref "IC8") (pin "23") (pinfunction "B1_23") (pintype "bidirectional"))
      (node (ref "R33") (pin "1") (pinfunction "1_1") (pintype "passive"))
    )
    (net (code "32") (name "Net-(IC8-B3)") (class "Default")
      (node (ref "IC8") (pin "19") (pinfunction "B4_19") (pintype "bidirectional"))
      (node (ref "IC8") (pin "20") (pinfunction "B3_20") (pintype "bidirectional"))
      (node (ref "R32") (pin "1") (pinfunction "1_1") (pintype "passive"))
    )
    (net (code "33") (name "Net-(IC8-B5)") (class "Default")
      (node (ref "IC8") (pin "17") (pinfunction "B6_17") (pintype "bidirectional"))
      (node (ref "IC8") (pin "18") (pinfunction "B5_18") (pintype "bidirectional"))
      (node (ref "R31") (pin "1") (pinfunction "1_1") (pintype "passive"))
    )
    (net (code "34") (name "Net-(IC8-B7)") (class "Default")
      (node (ref "IC8") (pin "14") (pinfunction "B8_14") (pintype "bidirectional"))
      (node (ref "IC8") (pin "15") (pinfunction "B7_15") (pintype "bidirectional"))
      (node (ref "R30") (pin "1") (pinfunction "1_1") (pintype "passive"))
    )
    (net (code "35") (name "Net-(IC8-DIR)") (class "Default")
      (node (ref "IC8") (pin "24") (pinfunction "DIR_24") (pintype "input"))
      (node (ref "R172") (pin "1") (pinfunction "1_1") (pintype "passive"))
      (node (ref "T29") (pin "3") (pinfunction "D_3") (pintype "passive"))
      (node (ref "T31") (pin "1") (pinfunction "G_1") (pintype "passive"))
    )
    (net (code "36") (name "Net-(IC9-1FSEN)") (class "Default")
      (node (ref "IC9") (pin "20") (pinfunction "3FSEN_20") (pintype "input"))
      (node (ref "IC9") (pin "22") (pinfunction "4FSEN_22") (pintype "input"))
      (node (ref "IC9") (pin "39") (pinfunction "1FSEN_39") (pintype "input"))
      (node (ref "IC9") (pin "41") (pinfunction "2FSEN_41") (pintype "input"))
      (node (ref "R157") (pin "1") (pinfunction "1_1") (pintype "passive"))
      (node (ref "R171") (pin "1") (pinfunction "1_1") (pintype "passive"))
    )
    (net (code "37") (name "Net-(IC10-A2)") (class "Default")
      (node (ref "IC10") (pin "3") (pinfunction "A2_3") (pintype "input"))
      (node (ref "IC11") (pin "14") (pinfunction "B2_14") (pintype "output"))
      (node (ref "IC17") (pin "3") (pinfunction "IN1_3") (pintype "input"))
      (node (ref "IC18") (pin "14") (pinfunction "OUT1_14") (pintype "output"))
      (node (ref "R30") (pin "2") (pinfunction "2_2") (pintype "passive"))
    )
    (net (code "38") (name "Net-(IC10-A3)") (class "Default")
      (node (ref "IC10") (pin "4") (pinfunction "A3_4") (pintype "input"))
      (node (ref "IC11") (pin "13") (pinfunction "B3_13") (pintype "output"))
      (node (ref "IC17") (pin "4") (pinfunction "IN2_4") (pintype "input"))
      (node (ref "IC18") (pin "13") (pinfunction "OUT2_13") (pintype "output"))
      (node (ref "R31") (pin "2") (pinfunction "2_2") (pintype "passive"))
    )
    (net (code "39") (name "Net-(IC10-A4)") (class "Default")
      (node (ref "IC10") (pin "5") (pinfunction "A4_5") (pintype "input"))
      (node (ref "IC11") (pin "12") (pinfunction "B4_12") (pintype "output"))
      (node (ref "IC17") (pin "5") (pinfunction "IN3_5") (pintype "input"))
      (node (ref "IC18") (pin "12") (pinfunction "OUT3_12") (pintype "output"))
      (node (ref "R32") (pin "2") (pinfunction "2_2") (pintype "passive"))
    )
    (net (code "40") (name "Net-(IC10-A5)") (class "Default")
      (node (ref "IC10") (pin "6") (pinfunction "A5_6") (pintype "input"))
      (node (ref "IC11") (pin "11") (pinfunction "B5_11") (pintype "output"))
      (node (ref "IC17") (pin "6") (pinfunction "IN4_6") (pintype "input"))
      (node (ref "IC18") (pin "11") (pinfunction "OUT4_11") (pintype "output"))
      (node (ref "R33") (pin "2") (pinfunction "2_2") (pintype "passive"))
    )
    (net (code "41") (name "Net-(IC10-B2)") (class "Default")
      (node (ref "IC10") (pin "14") (pinfunction "B2_14") (pintype "output"))
      (node (ref "IC17") (pin "14") (pinfunction "OUT1_14") (pintype "output"))
      (node (ref "IC9") (pin "35") (pinfunction "1D_35") (pintype "input"))
    )
    (net (code "42") (name "Net-(IC10-B3)") (class "Default")
      (node (ref "IC10") (pin "13") (pinfunction "B3_13") (pintype "output"))
      (node (ref "IC17") (pin "13") (pinfunction "OUT2_13") (pintype "output"))
      (node (ref "IC9") (pin "32") (pinfunction "2D_32") (pintype "input"))
    )
    (net (code "43") (name "Net-(IC10-B4)") (class "Default")
      (node (ref "IC10") (pin "12") (pinfunction "B4_12") (pintype "output"))
      (node (ref "IC17") (pin "12") (pinfunction "OUT3_12") (pintype "output"))
      (node (ref "IC9") (pin "28") (pinfunction "3D_28") (pintype "input"))
    )
    (net (code "44") (name "Net-(IC10-B5)") (class "Default")
      (node (ref "IC10") (pin "11") (pinfunction "B5_11") (pintype "output"))
      (node (ref "IC17") (pin "11") (pinfunction "OUT4_11") (pintype "output"))
      (node (ref "IC9") (pin "25") (pinfunction "4D_25") (pintype "input"))
    )
    (net (code "45") (name "Net-(IC11-A2)") (class "Default")
      (node (ref "IC11") (pin "3") (pinfunction "A2_3") (pintype "input"))
      (node (ref "IC18") (pin "3") (pinfunction "IN1_3") (pintype "input"))
      (node (ref "IC9") (pin "36") (pinfunction "1R_36") (pintype "output"))
    )
    (net (code "46") (name "Net-(IC11-A3)") (class "Default")
      (node (ref "IC11") (pin "4") (pinfunction "A3_4") (pintype "input"))
      (node (ref "IC18") (pin "4") (pinfunction "IN2_4") (pintype "input"))
      (node (ref "IC9") (pin "33") (pinfunction "2R_33") (pintype "output"))
    )
    (net (code "47") (name "Net-(IC11-A4)") (class "Default")
      (node (ref "IC11") (pin "5") (pinfunction "A4_5") (pintype "input"))
      (node (ref "IC18") (pin "5") (pinfunction "IN3_5") (pintype "input"))
      (node (ref "IC9") (pin "29") (pinfunction "3R_29") (pintype "output"))
    )
    (net (code "48") (name "Net-(IC11-A5)") (class "Default")
      (node (ref "IC11") (pin "6") (pinfunction "A5_6") (pintype "input"))
      (node (ref "IC18") (pin "6") (pinfunction "IN4_6") (pintype "input"))
      (node (ref "IC9") (pin "26") (pinfunction "4R_26") (pintype "output"))
    )
    (net (code "49") (name "Net-(IC11-EN2)") (class "Default")
      (node (ref "IC11") (pin "10") (pinfunction "EN2_10") (pintype "input"))
      (node (ref "IC14") (pin "4") (pinfunction "E_4") (pintype "open_emitter"))
      (node (ref "IC18") (pin "10") (pinfunction "ENB_10") (pintype "input"))
      (node (ref "R53") (pin "2") (pinfunction "2_2") (pintype "passive"))
      (node (ref "T29") (pin "1") (pinfunction "G_1") (pintype "passive"))
      (node (ref "T30") (pin "1") (pinfunction "G_1") (pintype "passive"))
    )
    (net (code "50") (name "Net-(IC14-A)") (class "Default")
      (node (ref "IC14") (pin "1") (pinfunction "A_1") (pintype "input"))
      (node (ref "R59") (pin "1") (pinfunction "1_1") (pintype "passive"))
    )
    (net (code "51") (name "Net-(LD6A-C)") (class "Default")
      (node (ref "LD6") (pin "1") (pinfunction "C_1") (pintype "passive"))
      (node (ref "R51") (pin "1") (pinfunction "1_1") (pintype "passive"))
    )
    (net (code "52") (name "Net-(LD6B-C)") (class "Default")
      (node (ref "LD6") (pin "3") (pinfunction "C_3") (pintype "passive"))
      (node (ref "R50") (pin "1") (pinfunction "1_1") (pintype "passive"))
    )
    (net (code "53") (name "Net-(T5-D)") (class "Default")
      (node (ref "R158") (pin "1") (pinfunction "1_1") (pintype "passive"))
      (node (ref "T5") (pin "3") (pinfunction "D_3") (pintype "passive"))
    )
    (net (code "54") (name "Net-(T6-D)") (class "Default")
      (node (ref "R161") (pin "1") (pinfunction "1_1") (pintype "passive"))
      (node (ref "T6") (pin "3") (pinfunction "D_3") (pintype "passive"))
    )
    (net (code "55") (name "Net-(T7-D)") (class "Default")
      (node (ref "R164") (pin "1") (pinfunction "1_1") (pintype "passive"))
      (node (ref "T7") (pin "3") (pinfunction "D_3") (pintype "passive"))
    )
    (net (code "56") (name "Net-(T8-D)") (class "Default")
      (node (ref "R168") (pin "1") (pinfunction "1_1") (pintype "passive"))
      (node (ref "T8") (pin "3") (pinfunction "D_3") (pintype "passive"))
    )
    (net (code "57") (name "Net-(T30-D)") (class "Default")
      (node (ref "R51") (pin "2") (pinfunction "2_2") (pintype "passive"))
      (node (ref "T30") (pin "3") (pinfunction "D_3") (pintype "passive"))
    )
    (net (code "58") (name "Net-(T31-D)") (class "Default")
      (node (ref "R50") (pin "2") (pinfunction "2_2") (pintype "passive"))
      (node (ref "T31") (pin "3") (pinfunction "D_3") (pintype "passive"))
    )
    (net (code "59") (name "P3V3") (class "Default")
      (node (ref "IC10") (pin "10") (pinfunction "EN2_10") (pintype "input"))
      (node (ref "IC10") (pin "16") (pinfunction "VDD2_16") (pintype "power_in"))
      (node (ref "IC11") (pin "1") (pinfunction "VDD1_1") (pintype "power_in"))
      (node (ref "IC17") (pin "10") (pinfunction "ENB_10") (pintype "input"))
      (node (ref "IC17") (pin "16") (pinfunction "VDDB_16") (pintype "power_in"))
      (node (ref "IC18") (pin "1") (pinfunction "VDDA_1") (pintype "power_in"))
      (node (ref "IC9") (pin "11") (pinfunction "VCC_11") (pintype "power_in"))
      (node (ref "IC9") (pin "15") (pinfunction "VCC_15") (pintype "power_in"))
      (node (ref "IC9") (pin "16") (pinfunction "VCC_16") (pintype "power_in"))
      (node (ref "IC9") (pin "2") (pinfunction "VCC_2") (pintype "power_in"))
      (node (ref "IC9") (pin "24") (pinfunction "VCC_24") (pintype "power_in"))
      (node (ref "IC9") (pin "30") (pinfunction "PDN_30") (pintype "input"))
      (node (ref "IC9") (pin "37") (pinfunction "VCC_37") (pintype "power_in"))
      (node (ref "IC9") (pin "45") (pinfunction "VCC_45") (pintype "power_in"))
      (node (ref "IC9") (pin "46") (pinfunction "VCC_46") (pintype "power_in"))
      (node (ref "R55") (pin "2") (pinfunction "2_2") (pintype "passive"))
      (node (ref "R59") (pin "2") (pinfunction "2_2") (pintype "passive"))
    )
    (net (code "60") (name "P5V0_ISO2") (class "Default")
      (node (ref "D4") (pin "4") (pinfunction "VCC_4") (pintype "power_in"))
      (node (ref "D5") (pin "4") (pinfunction "VCC_4") (pintype "power_in"))
      (node (ref "IC10") (pin "1") (pinfunction "VDD1_1") (pintype "power_in"))
      (node (ref "IC11") (pin "16") (pinfunction "VDD2_16") (pintype "power_in"))
      (node (ref "IC14") (pin "6") (pinfunction "C_6") (pintype "open_collector"))
      (node (ref "IC17") (pin "1") (pinfunction "VDDA_1") (pintype "power_in"))
      (node (ref "IC18") (pin "16") (pinfunction "VDDB_16") (pintype "power_in"))
      (node (ref "IC4") (pin "3") (pinfunction "VDD_3") (pintype "power_in"))
      (node (ref "IC8") (pin "16") (pinfunction "VCC_16") (pintype "power_in"))
      (node (ref "IC8") (pin "21") (pinfunction "VCC_21") (pintype "power_in"))
      (node (ref "LD6") (pin "2") (pinfunction "A_2") (pintype "passive"))
      (node (ref "LD6") (pin "4") (pinfunction "A_4") (pintype "passive"))
      (node (ref "R172") (pin "2") (pinfunction "2_2") (pintype "passive"))
      (node (ref "SW2") (pin "1") (pinfunction "1_1") (pintype "passive"))
      (node (ref "SW2") (pin "2") (pinfunction "2_2") (pintype "passive"))
      (node (ref "SW2") (pin "3") (pinfunction "3_3") (pintype "passive"))
      (node (ref "SW2") (pin "4") (pinfunction "4_4") (pintype "passive"))
    )
    (net (code "61") (name "unconnected-(IC9-NC-Pad17)") (class "Default")
      (node (ref "IC9") (pin "17") (pinfunction "NC_17") (pintype "passive"))
    )
    (net (code "62") (name "unconnected-(IC9-NC-Pad44)") (class "Default")
      (node (ref "IC9") (pin "44") (pinfunction "NC_44") (pintype "passive"))
    )
    (net (code "63") (name "unconnected-(IC10-NC-Pad7)") (class "Default")
      (node (ref "IC10") (pin "7") (pinfunction "NC_7") (pintype "passive"))
    )
    (net (code "64") (name "unconnected-(IC11-NC-Pad7)") (class "Default")
      (node (ref "IC11") (pin "7") (pinfunction "NC_7") (pintype "passive"))
    )
    (net (code "65") (name "unconnected-(IC17-IC-Pad7)") (class "Default")
      (node (ref "IC17") (pin "7") (pinfunction "IC_7") (pintype "passive"))
    )
    (net (code "66") (name "unconnected-(IC18-IC-Pad7)") (class "Default")
      (node (ref "IC18") (pin "7") (pinfunction "IC_7") (pintype "passive"))
    )
  )
)
